# MazeBot_Main_Board.net
KiCad netlist of a schematic drawn in EAGLE
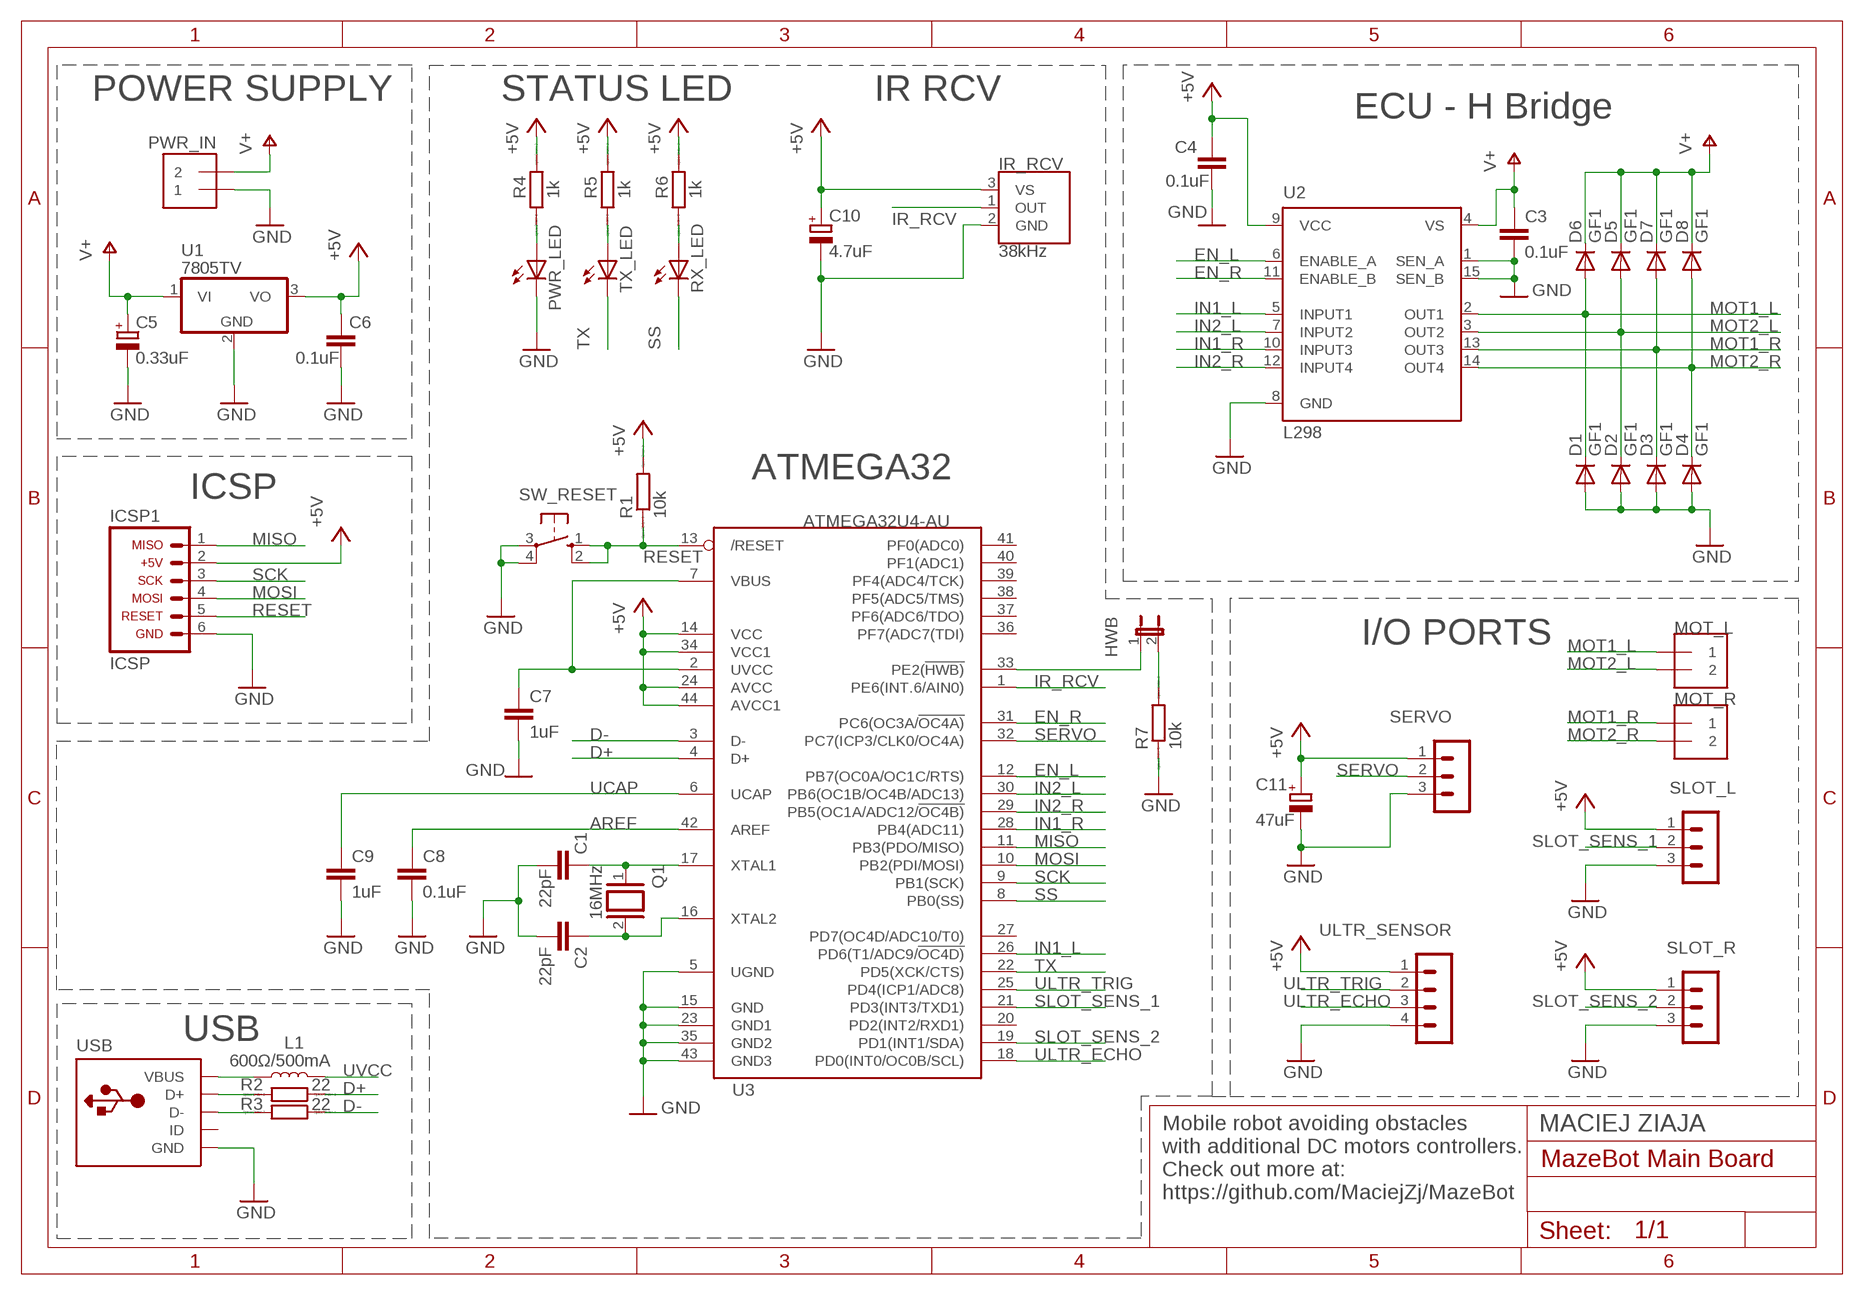
[diagram p0: schematic, sheet 1]

(export (version "E")
  (design (tool "Eeschema 10.0.6"))
  (components
    (comp (ref "C1")
      (value "22pF")
      (footprint "eagle-import:C025-024X044")
      (libsource (lib "eagle-import") (part "C-EU025-024X044"))
    )
    (comp (ref "C2")
      (value "22pF")
      (footprint "eagle-import:C025-024X044")
      (libsource (lib "eagle-import") (part "C-EU025-024X044"))
    )
    (comp (ref "C3")
      (value "0.1uF")
      (footprint "eagle-import:C025-024X044")
      (libsource (lib "eagle-import") (part "C-EU025-024X044"))
    )
    (comp (ref "C4")
      (value "0.1uF")
      (footprint "eagle-import:C025-024X044")
      (libsource (lib "eagle-import") (part "C-EU025-024X044"))
    )
    (comp (ref "C5")
      (value "0.33uF")
      (footprint "eagle-import:UD-4X5,8_NICHICON")
      (libsource (lib "eagle-import") (part "CPOL-EUUD-4X5,8"))
    )
    (comp (ref "C6")
      (value "0.1uF")
      (footprint "eagle-import:C025-024X044")
      (libsource (lib "eagle-import") (part "C-EU025-024X044"))
    )
    (comp (ref "C7")
      (value "1uF")
      (footprint "eagle-import:C025-024X044")
      (libsource (lib "eagle-import") (part "C-EU025-024X044"))
    )
    (comp (ref "C8")
      (value "0.1uF")
      (footprint "eagle-import:C025-024X044")
      (libsource (lib "eagle-import") (part "C-EU025-024X044"))
    )
    (comp (ref "C9")
      (value "1uF")
      (footprint "eagle-import:C025-024X044")
      (libsource (lib "eagle-import") (part "C-EU025-024X044"))
    )
    (comp (ref "C10")
      (value "4.7uF")
      (footprint "eagle-import:UD-6,3X5,8_NICHICON")
      (libsource (lib "eagle-import") (part "CPOL-EUUD-6,3X8,8"))
    )
    (comp (ref "C11")
      (value "47uF")
      (footprint "eagle-import:UD-6,3X5,8_NICHICON")
      (libsource (lib "eagle-import") (part "CPOL-EUUD-6,3X8,8"))
    )
    (comp (ref "D1")
      (value "GF1")
      (footprint "eagle-import:SMA-DO214AC")
      (libsource (lib "eagle-import") (part "GF1"))
    )
    (comp (ref "D2")
      (value "GF1")
      (footprint "eagle-import:SMA-DO214AC")
      (libsource (lib "eagle-import") (part "GF1"))
    )
    (comp (ref "D3")
      (value "GF1")
      (footprint "eagle-import:SMA-DO214AC")
      (libsource (lib "eagle-import") (part "GF1"))
    )
    (comp (ref "D4")
      (value "GF1")
      (footprint "eagle-import:SMA-DO214AC")
      (libsource (lib "eagle-import") (part "GF1"))
    )
    (comp (ref "D5")
      (value "GF1")
      (footprint "eagle-import:SMA-DO214AC")
      (libsource (lib "eagle-import") (part "GF1"))
    )
    (comp (ref "D6")
      (value "GF1")
      (footprint "eagle-import:SMA-DO214AC")
      (libsource (lib "eagle-import") (part "GF1"))
    )
    (comp (ref "D7")
      (value "GF1")
      (footprint "eagle-import:SMA-DO214AC")
      (libsource (lib "eagle-import") (part "GF1"))
    )
    (comp (ref "D8")
      (value "GF1")
      (footprint "eagle-import:SMA-DO214AC")
      (libsource (lib "eagle-import") (part "GF1"))
    )
    (comp (ref "HWB")
      (value "JP1E")
      (footprint "eagle-import:JP1")
      (libsource (lib "eagle-import") (part "JP1E"))
    )
    (comp (ref "ICSP1")
      (value "ARDUINO_CONN-ICSP")
      (footprint "eagle-import:CONN-2X03")
      (libsource (lib "eagle-import") (part "ARDUINO_CONN-ICSP"))
    )
    (comp (ref "IR_RCV")
      (value "38kHz")
      (footprint "eagle-import:TSOP382")
      (libsource (lib "eagle-import") (part "TSOP38238"))
    )
    (comp (ref "L1")
      (value "600Ω/500mA")
      (footprint "eagle-import:0805")
      (libsource (lib "eagle-import") (part "INDUCTOR-0805-3.3UH"))
    )
    (comp (ref "MOT_L")
      (value "1X2-3.5MM")
      (footprint "eagle-import:1X2-3.5MM")
      (libsource (lib "eagle-import") (part "1X2-3.5MM"))
    )
    (comp (ref "MOT_R")
      (value "1X2-3.5MM")
      (footprint "eagle-import:1X2-3.5MM")
      (libsource (lib "eagle-import") (part "1X2-3.5MM"))
    )
    (comp (ref "PWR_IN")
      (value "1X2-3.5MM")
      (footprint "eagle-import:1X2-3.5MM")
      (libsource (lib "eagle-import") (part "1X2-3.5MM"))
    )
    (comp (ref "PWR_LED")
      (value "LEDCHIP-LED0805")
      (footprint "eagle-import:CHIP-LED0805")
      (libsource (lib "eagle-import") (part "LEDCHIP-LED0805"))
    )
    (comp (ref "Q1")
      (value "16MHz")
      (footprint "eagle-import:QS")
      (libsource (lib "eagle-import") (part "XTAL/S"))
    )
    (comp (ref "R1")
      (value "10k")
      (footprint "eagle-import:R1206")
      (libsource (lib "eagle-import") (part "RR1206"))
    )
    (comp (ref "R2")
      (value "22")
      (footprint "eagle-import:R1206")
      (libsource (lib "eagle-import") (part "RR1206"))
    )
    (comp (ref "R3")
      (value "22")
      (footprint "eagle-import:R1206")
      (libsource (lib "eagle-import") (part "RR1206"))
    )
    (comp (ref "R4")
      (value "1k")
      (footprint "eagle-import:R1206")
      (libsource (lib "eagle-import") (part "RR1206"))
    )
    (comp (ref "R5")
      (value "1k")
      (footprint "eagle-import:R1206")
      (libsource (lib "eagle-import") (part "RR1206"))
    )
    (comp (ref "R6")
      (value "1k")
      (footprint "eagle-import:R1206")
      (libsource (lib "eagle-import") (part "RR1206"))
    )
    (comp (ref "R7")
      (value "10k")
      (footprint "eagle-import:R1206")
      (libsource (lib "eagle-import") (part "RR1206"))
    )
    (comp (ref "RX_LED")
      (value "LEDCHIP-LED0805")
      (footprint "eagle-import:CHIP-LED0805")
      (libsource (lib "eagle-import") (part "LEDCHIP-LED0805"))
    )
    (comp (ref "SERVO")
      (value "MA03-1")
      (footprint "eagle-import:MA03-1")
      (libsource (lib "eagle-import") (part "MA03-1"))
    )
    (comp (ref "SLOT_L")
      (value "MA03-1")
      (footprint "eagle-import:MA03-1")
      (libsource (lib "eagle-import") (part "MA03-1"))
    )
    (comp (ref "SLOT_R")
      (value "MA03-1")
      (footprint "eagle-import:MA03-1")
      (libsource (lib "eagle-import") (part "MA03-1"))
    )
    (comp (ref "SW_RESET")
      (value "10-XX")
      (footprint "eagle-import:B3F-10XX")
      (fields (field (name "MPN") "B3F-1000"))
      (libsource (lib "eagle-import") (part "10-XX"))
    )
    (comp (ref "TX_LED")
      (value "LEDCHIP-LED0805")
      (footprint "eagle-import:CHIP-LED0805")
      (libsource (lib "eagle-import") (part "LEDCHIP-LED0805"))
    )
    (comp (ref "U1")
      (value "7805TV")
      (footprint "eagle-import:TO220V")
      (libsource (lib "eagle-import") (part "78TV05"))
    )
    (comp (ref "U2")
      (value "L298")
      (footprint "eagle-import:MULTIWATT-15")
      (fields (field (name "MPN") "L298N"))
      (libsource (lib "eagle-import") (part "L298"))
    )
    (comp (ref "U3")
      (value "ATMEGA32U4-AU")
      (footprint "eagle-import:TQFP44")
      (libsource (lib "eagle-import") (part "ATMEGA32U4-AU"))
    )
    (comp (ref "ULTR_SENSOR")
      (value "MA04-1")
      (footprint "eagle-import:MA04-1")
      (libsource (lib "eagle-import") (part "MA04-1"))
    )
    (comp (ref "USB")
      (value "USBMINIB")
      (footprint "eagle-import:USB-MINIB")
      (libsource (lib "eagle-import") (part "USBMINIB"))
    )
  )
  (nets
    (net (code "1") (name "+5V") (class "Default")
      (node (ref "C10") (pin "+") (pinfunction "+_+") (pintype "passive"))
      (node (ref "C11") (pin "+") (pinfunction "+_+") (pintype "passive"))
      (node (ref "C4") (pin "1") (pinfunction "1_1") (pintype "passive"))
      (node (ref "C6") (pin "1") (pinfunction "1_1") (pintype "passive"))
      (node (ref "ICSP1") (pin "2") (pinfunction "2_2") (pintype "passive"))
      (node (ref "IR_RCV") (pin "3") (pinfunction "VS_3") (pintype "bidirectional"))
      (node (ref "R1") (pin "2") (pinfunction "2_2") (pintype "passive"))
      (node (ref "R4") (pin "2") (pinfunction "2_2") (pintype "passive"))
      (node (ref "R5") (pin "2") (pinfunction "2_2") (pintype "passive"))
      (node (ref "R6") (pin "2") (pinfunction "2_2") (pintype "passive"))
      (node (ref "SERVO") (pin "1") (pinfunction "1_1") (pintype "passive"))
      (node (ref "SLOT_L") (pin "1") (pinfunction "1_1") (pintype "passive"))
      (node (ref "SLOT_R") (pin "1") (pinfunction "1_1") (pintype "passive"))
      (node (ref "U1") (pin "3") (pinfunction "VO_3") (pintype "passive"))
      (node (ref "U2") (pin "9") (pinfunction "VCC_9") (pintype "power_in"))
      (node (ref "U3") (pin "14") (pinfunction "VCC_14") (pintype "bidirectional"))
      (node (ref "U3") (pin "24") (pinfunction "AVCC_24") (pintype "bidirectional"))
      (node (ref "U3") (pin "34") (pinfunction "VCC1_34") (pintype "bidirectional"))
      (node (ref "U3") (pin "44") (pinfunction "AVCC1_44") (pintype "bidirectional"))
      (node (ref "ULTR_SENSOR") (pin "1") (pinfunction "1_1") (pintype "passive"))
    )
    (net (code "2") (name "/AREF") (class "Default")
      (node (ref "C8") (pin "1") (pinfunction "1_1") (pintype "passive"))
      (node (ref "U3") (pin "42") (pinfunction "AREF_42") (pintype "bidirectional"))
    )
    (net (code "3") (name "/D+") (class "Default")
      (node (ref "R2") (pin "1") (pinfunction "1_1") (pintype "passive"))
      (node (ref "U3") (pin "4") (pinfunction "D+_4") (pintype "bidirectional"))
    )
    (net (code "4") (name "/D-") (class "Default")
      (node (ref "R3") (pin "1") (pinfunction "1_1") (pintype "passive"))
      (node (ref "U3") (pin "3") (pinfunction "D-_3") (pintype "bidirectional"))
    )
    (net (code "5") (name "/EN_L") (class "Default")
      (node (ref "U2") (pin "6") (pinfunction "ENABLE_A_6") (pintype "input"))
      (node (ref "U3") (pin "12") (pinfunction "PB7(OC0A/OC1C/RTS)_12") (pintype "bidirectional"))
    )
    (net (code "6") (name "/EN_R") (class "Default")
      (node (ref "U2") (pin "11") (pinfunction "ENABLE_B_11") (pintype "input"))
      (node (ref "U3") (pin "31") (pinfunction "PC6(OC3A/~{OC4A})_31") (pintype "bidirectional"))
    )
    (net (code "7") (name "/IN1_L") (class "Default")
      (node (ref "U2") (pin "5") (pinfunction "INPUT1_5") (pintype "input"))
      (node (ref "U3") (pin "26") (pinfunction "PD6(T1/ADC9/~{OC4D})_26") (pintype "bidirectional"))
    )
    (net (code "8") (name "/IN1_R") (class "Default")
      (node (ref "U2") (pin "10") (pinfunction "INPUT3_10") (pintype "input"))
      (node (ref "U3") (pin "28") (pinfunction "PB4(ADC11)_28") (pintype "bidirectional"))
    )
    (net (code "9") (name "/IN2_L") (class "Default")
      (node (ref "U2") (pin "7") (pinfunction "INPUT2_7") (pintype "input"))
      (node (ref "U3") (pin "30") (pinfunction "PB6(OC1B/OC4B/ADC13)_30") (pintype "bidirectional"))
    )
    (net (code "10") (name "/IN2_R") (class "Default")
      (node (ref "U2") (pin "12") (pinfunction "INPUT4_12") (pintype "input"))
      (node (ref "U3") (pin "29") (pinfunction "PB5(OC1A/ADC12/~{OC4B})_29") (pintype "bidirectional"))
    )
    (net (code "11") (name "/IR_RCV") (class "Default")
      (node (ref "IR_RCV") (pin "1") (pinfunction "OUT_1") (pintype "bidirectional"))
      (node (ref "U3") (pin "1") (pinfunction "PE6(INT.6/AIN0)_1") (pintype "bidirectional"))
    )
    (net (code "12") (name "/MISO") (class "Default")
      (node (ref "ICSP1") (pin "1") (pinfunction "1_1") (pintype "passive"))
      (node (ref "U3") (pin "11") (pinfunction "PB3(PDO/MISO)_11") (pintype "bidirectional"))
    )
    (net (code "13") (name "/MOSI") (class "Default")
      (node (ref "ICSP1") (pin "4") (pinfunction "4_4") (pintype "passive"))
      (node (ref "U3") (pin "10") (pinfunction "PB2(PDI/MOSI)_10") (pintype "bidirectional"))
    )
    (net (code "14") (name "/MOT1_L") (class "Default")
      (node (ref "D1") (pin "K") (pinfunction "C_K") (pintype "passive"))
      (node (ref "D6") (pin "A") (pinfunction "A_A") (pintype "passive"))
      (node (ref "MOT_L") (pin "1") (pinfunction "1_1") (pintype "passive"))
      (node (ref "U2") (pin "2") (pinfunction "OUT1_2") (pintype "output"))
    )
    (net (code "15") (name "/MOT1_R") (class "Default")
      (node (ref "D3") (pin "K") (pinfunction "C_K") (pintype "passive"))
      (node (ref "D7") (pin "A") (pinfunction "A_A") (pintype "passive"))
      (node (ref "MOT_R") (pin "1") (pinfunction "1_1") (pintype "passive"))
      (node (ref "U2") (pin "13") (pinfunction "OUT3_13") (pintype "output"))
    )
    (net (code "16") (name "/MOT2_L") (class "Default")
      (node (ref "D2") (pin "K") (pinfunction "C_K") (pintype "passive"))
      (node (ref "D5") (pin "A") (pinfunction "A_A") (pintype "passive"))
      (node (ref "MOT_L") (pin "2") (pinfunction "2_2") (pintype "passive"))
      (node (ref "U2") (pin "3") (pinfunction "OUT2_3") (pintype "output"))
    )
    (net (code "17") (name "/MOT2_R") (class "Default")
      (node (ref "D4") (pin "K") (pinfunction "C_K") (pintype "passive"))
      (node (ref "D8") (pin "A") (pinfunction "A_A") (pintype "passive"))
      (node (ref "MOT_R") (pin "2") (pinfunction "2_2") (pintype "passive"))
      (node (ref "U2") (pin "14") (pinfunction "OUT4_14") (pintype "output"))
    )
    (net (code "18") (name "/RESET") (class "Default")
      (node (ref "ICSP1") (pin "5") (pinfunction "5_5") (pintype "passive"))
      (node (ref "R1") (pin "1") (pinfunction "1_1") (pintype "passive"))
      (node (ref "SW_RESET") (pin "1") (pinfunction "S_1") (pintype "passive"))
      (node (ref "SW_RESET") (pin "2") (pinfunction "S1_2") (pintype "passive"))
      (node (ref "U3") (pin "13") (pinfunction "/RESET_13") (pintype "bidirectional"))
    )
    (net (code "19") (name "/SCK") (class "Default")
      (node (ref "ICSP1") (pin "3") (pinfunction "3_3") (pintype "passive"))
      (node (ref "U3") (pin "9") (pinfunction "PB1(SCK)_9") (pintype "bidirectional"))
    )
    (net (code "20") (name "/SERVO") (class "Default")
      (node (ref "SERVO") (pin "2") (pinfunction "2_2") (pintype "passive"))
      (node (ref "U3") (pin "32") (pinfunction "PC7(ICP3/CLK0/OC4A)_32") (pintype "bidirectional"))
    )
    (net (code "21") (name "/SLOT_SENS_1") (class "Default")
      (node (ref "SLOT_L") (pin "2") (pinfunction "2_2") (pintype "passive"))
      (node (ref "U3") (pin "21") (pinfunction "PD3(INT3/TXD1)_21") (pintype "bidirectional"))
    )
    (net (code "22") (name "/SLOT_SENS_2") (class "Default")
      (node (ref "SLOT_R") (pin "2") (pinfunction "2_2") (pintype "passive"))
      (node (ref "U3") (pin "19") (pinfunction "PD1(INT1/SDA)_19") (pintype "bidirectional"))
    )
    (net (code "23") (name "/SS") (class "Default")
      (node (ref "RX_LED") (pin "C") (pinfunction "C_C") (pintype "passive"))
      (node (ref "U3") (pin "8") (pinfunction "PB0(SS)_8") (pintype "bidirectional"))
    )
    (net (code "24") (name "/TX") (class "Default")
      (node (ref "TX_LED") (pin "C") (pinfunction "C_C") (pintype "passive"))
      (node (ref "U3") (pin "22") (pinfunction "PD5(XCK/CTS)_22") (pintype "bidirectional"))
    )
    (net (code "25") (name "/UCAP") (class "Default")
      (node (ref "C9") (pin "1") (pinfunction "1_1") (pintype "passive"))
      (node (ref "U3") (pin "6") (pinfunction "UCAP_6") (pintype "bidirectional"))
    )
    (net (code "26") (name "/ULTR_ECHO") (class "Default")
      (node (ref "U3") (pin "18") (pinfunction "PD0(INT0/OC0B/SCL)_18") (pintype "bidirectional"))
      (node (ref "ULTR_SENSOR") (pin "3") (pinfunction "3_3") (pintype "passive"))
    )
    (net (code "27") (name "/ULTR_TRIG") (class "Default")
      (node (ref "U3") (pin "25") (pinfunction "PD4(ICP1/ADC8)_25") (pintype "bidirectional"))
      (node (ref "ULTR_SENSOR") (pin "2") (pinfunction "2_2") (pintype "passive"))
    )
    (net (code "28") (name "/UVCC") (class "Default")
      (node (ref "C7") (pin "1") (pinfunction "1_1") (pintype "passive"))
      (node (ref "L1") (pin "2") (pinfunction "2_2") (pintype "passive"))
      (node (ref "U3") (pin "2") (pinfunction "UVCC_2") (pintype "bidirectional"))
      (node (ref "U3") (pin "7") (pinfunction "VBUS_7") (pintype "bidirectional"))
    )
    (net (code "29") (name "GND") (class "Default")
      (node (ref "C1") (pin "1") (pinfunction "1_1") (pintype "passive"))
      (node (ref "C10") (pin "-") (pinfunction "-_-") (pintype "passive"))
      (node (ref "C11") (pin "-") (pinfunction "-_-") (pintype "passive"))
      (node (ref "C2") (pin "2") (pinfunction "2_2") (pintype "passive"))
      (node (ref "C3") (pin "2") (pinfunction "2_2") (pintype "passive"))
      (node (ref "C4") (pin "2") (pinfunction "2_2") (pintype "passive"))
      (node (ref "C5") (pin "-") (pinfunction "-_-") (pintype "passive"))
      (node (ref "C6") (pin "2") (pinfunction "2_2") (pintype "passive"))
      (node (ref "C7") (pin "2") (pinfunction "2_2") (pintype "passive"))
      (node (ref "C8") (pin "2") (pinfunction "2_2") (pintype "passive"))
      (node (ref "C9") (pin "2") (pinfunction "2_2") (pintype "passive"))
      (node (ref "D1") (pin "A") (pinfunction "A_A") (pintype "passive"))
      (node (ref "D2") (pin "A") (pinfunction "A_A") (pintype "passive"))
      (node (ref "D3") (pin "A") (pinfunction "A_A") (pintype "passive"))
      (node (ref "D4") (pin "A") (pinfunction "A_A") (pintype "passive"))
      (node (ref "ICSP1") (pin "6") (pinfunction "6_6") (pintype "passive"))
      (node (ref "IR_RCV") (pin "2") (pinfunction "GND_2") (pintype "bidirectional"))
      (node (ref "PWR_IN") (pin "1") (pinfunction "1_1") (pintype "passive"))
      (node (ref "PWR_LED") (pin "C") (pinfunction "C_C") (pintype "passive"))
      (node (ref "R7") (pin "1") (pinfunction "1_1") (pintype "passive"))
      (node (ref "SERVO") (pin "3") (pinfunction "3_3") (pintype "passive"))
      (node (ref "SLOT_L") (pin "3") (pinfunction "3_3") (pintype "passive"))
      (node (ref "SLOT_R") (pin "3") (pinfunction "3_3") (pintype "passive"))
      (node (ref "SW_RESET") (pin "3") (pinfunction "P_3") (pintype "passive"))
      (node (ref "SW_RESET") (pin "4") (pinfunction "P1_4") (pintype "passive"))
      (node (ref "U1") (pin "2") (pinfunction "GND_2") (pintype "passive"))
      (node (ref "U2") (pin "1") (pinfunction "SEN_A_1") (pintype "input"))
      (node (ref "U2") (pin "15") (pinfunction "SEN_B_15") (pintype "input"))
      (node (ref "U2") (pin "8") (pinfunction "GND_8") (pintype "power_in"))
      (node (ref "U3") (pin "15") (pinfunction "GND_15") (pintype "bidirectional"))
      (node (ref "U3") (pin "23") (pinfunction "GND1_23") (pintype "bidirectional"))
      (node (ref "U3") (pin "35") (pinfunction "GND2_35") (pintype "bidirectional"))
      (node (ref "U3") (pin "43") (pinfunction "GND3_43") (pintype "bidirectional"))
      (node (ref "U3") (pin "5") (pinfunction "UGND_5") (pintype "bidirectional"))
      (node (ref "ULTR_SENSOR") (pin "4") (pinfunction "4_4") (pintype "passive"))
      (node (ref "USB") (pin "GND") (pinfunction "GND_GND") (pintype "power_in"))
    )
    (net (code "30") (name "Net-(HWB-Pad2)") (class "Default")
      (node (ref "HWB") (pin "2") (pinfunction "2_2") (pintype "passive"))
      (node (ref "R7") (pin "2") (pinfunction "2_2") (pintype "passive"))
    )
    (net (code "31") (name "Net-(L1-Pad1)") (class "Default")
      (node (ref "L1") (pin "1") (pinfunction "1_1") (pintype "passive"))
      (node (ref "USB") (pin "VBUS") (pinfunction "VBUS_VBUS") (pintype "power_in"))
    )
    (net (code "32") (name "Net-(PWR_LED-PadA)") (class "Default")
      (node (ref "PWR_LED") (pin "A") (pinfunction "A_A") (pintype "passive"))
      (node (ref "R4") (pin "1") (pinfunction "1_1") (pintype "passive"))
    )
    (net (code "33") (name "Net-(R2-Pad2)") (class "Default")
      (node (ref "R2") (pin "2") (pinfunction "2_2") (pintype "passive"))
      (node (ref "USB") (pin "D+") (pinfunction "D+_D+") (pintype "bidirectional"))
    )
    (net (code "34") (name "Net-(R3-Pad2)") (class "Default")
      (node (ref "R3") (pin "2") (pinfunction "2_2") (pintype "passive"))
      (node (ref "USB") (pin "D-") (pinfunction "D-_D-") (pintype "bidirectional"))
    )
    (net (code "35") (name "Net-(R5-Pad1)") (class "Default")
      (node (ref "R5") (pin "1") (pinfunction "1_1") (pintype "passive"))
      (node (ref "TX_LED") (pin "A") (pinfunction "A_A") (pintype "passive"))
    )
    (net (code "36") (name "Net-(R6-Pad1)") (class "Default")
      (node (ref "R6") (pin "1") (pinfunction "1_1") (pintype "passive"))
      (node (ref "RX_LED") (pin "A") (pinfunction "A_A") (pintype "passive"))
    )
    (net (code "37") (name "Net-(U3-PE2(~{HWB}))") (class "Default")
      (node (ref "HWB") (pin "1") (pinfunction "1_1") (pintype "passive"))
      (node (ref "U3") (pin "33") (pinfunction "PE2(~{HWB})_33") (pintype "bidirectional"))
    )
    (net (code "38") (name "Net-(U3-XTAL1)") (class "Default")
      (node (ref "C1") (pin "2") (pinfunction "2_2") (pintype "passive"))
      (node (ref "Q1") (pin "1") (pinfunction "1_1") (pintype "passive"))
      (node (ref "U3") (pin "17") (pinfunction "XTAL1_17") (pintype "bidirectional"))
    )
    (net (code "39") (name "Net-(U3-XTAL2)") (class "Default")
      (node (ref "C2") (pin "1") (pinfunction "1_1") (pintype "passive"))
      (node (ref "Q1") (pin "2") (pinfunction "2_2") (pintype "passive"))
      (node (ref "U3") (pin "16") (pinfunction "XTAL2_16") (pintype "bidirectional"))
    )
    (net (code "40") (name "V+") (class "Default")
      (node (ref "C3") (pin "1") (pinfunction "1_1") (pintype "passive"))
      (node (ref "C5") (pin "+") (pinfunction "+_+") (pintype "passive"))
      (node (ref "D5") (pin "K") (pinfunction "C_K") (pintype "passive"))
      (node (ref "D6") (pin "K") (pinfunction "C_K") (pintype "passive"))
      (node (ref "D7") (pin "K") (pinfunction "C_K") (pintype "passive"))
      (node (ref "D8") (pin "K") (pinfunction "C_K") (pintype "passive"))
      (node (ref "PWR_IN") (pin "2") (pinfunction "2_2") (pintype "passive"))
      (node (ref "U1") (pin "1") (pinfunction "VI_1") (pintype "input"))
      (node (ref "U2") (pin "4") (pinfunction "VS_4") (pintype "power_in"))
    )
    (net (code "41") (name "unconnected-(U3-PD2(INT2{slash}RXD1)-Pad20)") (class "Default")
      (node (ref "U3") (pin "20") (pinfunction "PD2(INT2/RXD1)_20") (pintype "bidirectional"))
    )
    (net (code "42") (name "unconnected-(U3-PD7(OC4D{slash}ADC10{slash}T0)-Pad27)") (class "Default")
      (node (ref "U3") (pin "27") (pinfunction "PD7(OC4D/ADC10/T0)_27") (pintype "bidirectional"))
    )
    (net (code "43") (name "unconnected-(U3-PF0(ADC0)-Pad41)") (class "Default")
      (node (ref "U3") (pin "41") (pinfunction "PF0(ADC0)_41") (pintype "bidirectional"))
    )
    (net (code "44") (name "unconnected-(U3-PF1(ADC1)-Pad40)") (class "Default")
      (node (ref "U3") (pin "40") (pinfunction "PF1(ADC1)_40") (pintype "bidirectional"))
    )
    (net (code "45") (name "unconnected-(U3-PF4(ADC4{slash}TCK)-Pad39)") (class "Default")
      (node (ref "U3") (pin "39") (pinfunction "PF4(ADC4/TCK)_39") (pintype "bidirectional"))
    )
    (net (code "46") (name "unconnected-(U3-PF5(ADC5{slash}TMS)-Pad38)") (class "Default")
      (node (ref "U3") (pin "38") (pinfunction "PF5(ADC5/TMS)_38") (pintype "bidirectional"))
    )
    (net (code "47") (name "unconnected-(U3-PF6(ADC6{slash}TDO)-Pad37)") (class "Default")
      (node (ref "U3") (pin "37") (pinfunction "PF6(ADC6/TDO)_37") (pintype "bidirectional"))
    )
    (net (code "48") (name "unconnected-(U3-PF7(ADC7(TDI)-Pad36)") (class "Default")
      (node (ref "U3") (pin "36") (pinfunction "PF7(ADC7(TDI)_36") (pintype "bidirectional"))
    )
    (net (code "49") (name "unconnected-(USB-PadID)") (class "Default")
      (node (ref "USB") (pin "ID") (pinfunction "ID_ID") (pintype "bidirectional"))
    )
  )
)
